# RPI_3_Backpower.net
KiCad netlist of a schematic drawn in Altium Designer
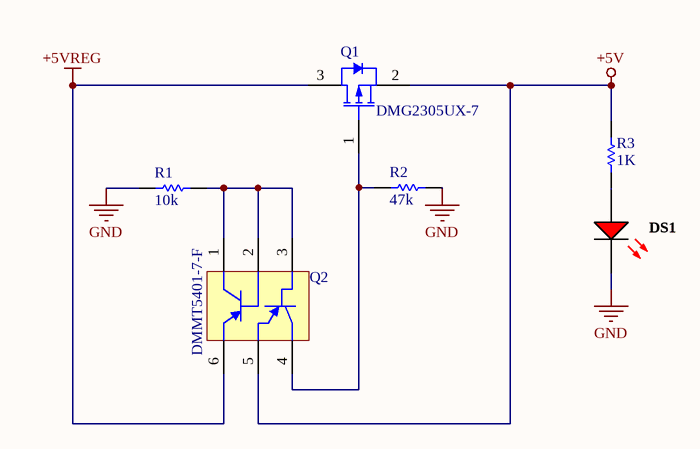
[diagram p0: RPI 3 Backpower.SchDoc]

(export (version "E")
  (design (tool "Eeschema 10.0.6"))
  (components
    (comp (ref "DS1")
      (value "APG1608SURKC/T")
      (footprint "KING-LED0603-25-RED_V")
      (fields (field (name "MANUFACTURER") "Kingbright"))
      (libsource (lib "Altium Content Vault") (part "KING-LED_RED_A1K2-2"))
    )
    (comp (ref "Q1")
      (value "DMG2305UX-7")
      (footprint "DIOD-SOT23-3_A_V")
      (description "P-Channel Enhancement Mode MOSFET, 20 V, -55 to 150 degC, 3-Pin SOT23, RoHS, Tape and Reel")
      (libsource (lib "Altium Content Vault") (part "PEMOS-GSD-3"))
    )
    (comp (ref "Q2")
      (value "DMMT5401-7-F")
      (footprint "DIOD-SOT-26-6_N")
      (fields (field (name "TOLERANCE") "1%"))
      (libsource (lib "Altium Content Vault") (part "DIOD-DMMT5401-SOT-26-6"))
    )
    (comp (ref "R1")
      (value "10k")
      (footprint "RESC1609X55X30LL15T15")
      (description "Chip Resistor, 10 KOhm, +/- 1%, 0.1 W, -55 to 155 degC, 0603 (1608 Metric), RoHS, Tape and Reel")
      (fields (field (name "TOLERANCE") "1%") (field (name "MANUFACTURER") "Panasonic"))
      (libsource (lib "Altium Content Vault") (part "RES-2"))
    )
    (comp (ref "R2")
      (value "47k")
      (footprint "RESC1608X55X25LL10T15")
      (fields (field (name "MANUFACTURER") "Yageo") (field (name "PART NUMBER") "AC0603FR-0747KL"))
      (libsource (lib "Altium Content Vault") (part "RES"))
    )
    (comp (ref "R3")
      (value "1K")
      (footprint "RESC1608X55X30LL15T15")
      (fields (field (name "PART NUMBER") "ERJ-3EKF1001V") (field (name "MANUFACTURER") "Panasonic"))
      (libsource (lib "Altium Content Vault") (part "RES"))
    )
  )
  (nets
    (net (code "1") (name "+5V") (class "Default")
      (node (ref "Q1") (pin "2") (pinfunction "SOURCE_2") (pintype "passive"))
      (node (ref "Q2") (pin "5") (pinfunction "E2_5") (pintype "passive"))
      (node (ref "R3") (pin "2") (pinfunction "2_2") (pintype "passive"))
    )
    (net (code "2") (name "+5VREG") (class "Default")
      (node (ref "Q1") (pin "3") (pinfunction "DRAIN_3") (pintype "passive"))
      (node (ref "Q2") (pin "6") (pinfunction "E1_6") (pintype "passive"))
    )
    (net (code "3") (name "GND") (class "Default")
      (node (ref "DS1") (pin "2") (pinfunction "K_2") (pintype "passive"))
      (node (ref "R1") (pin "1") (pinfunction "1_1") (pintype "passive"))
      (node (ref "R2") (pin "1") (pinfunction "1_1") (pintype "passive"))
    )
    (net (code "4") (name "Net-(DS1-A)") (class "Default")
      (node (ref "DS1") (pin "1") (pinfunction "A_1") (pintype "passive"))
      (node (ref "R3") (pin "1") (pinfunction "1_1") (pintype "passive"))
    )
    (net (code "5") (name "Net-(Q1-GATE)") (class "Default")
      (node (ref "Q1") (pin "1") (pinfunction "GATE_1") (pintype "passive"))
      (node (ref "Q2") (pin "4") (pinfunction "C2_4") (pintype "passive"))
      (node (ref "R2") (pin "2") (pinfunction "2_2") (pintype "passive"))
    )
    (net (code "6") (name "Net-(Q2-B1)") (class "Default")
      (node (ref "Q2") (pin "1") (pinfunction "C1_1") (pintype "passive"))
      (node (ref "Q2") (pin "2") (pinfunction "B1_2") (pintype "passive"))
      (node (ref "Q2") (pin "3") (pinfunction "B2_3") (pintype "passive"))
      (node (ref "R1") (pin "2") (pinfunction "2_2") (pintype "passive"))
    )
  )
)
